# PIC32.net
KiCad netlist of a schematic drawn in EAGLE
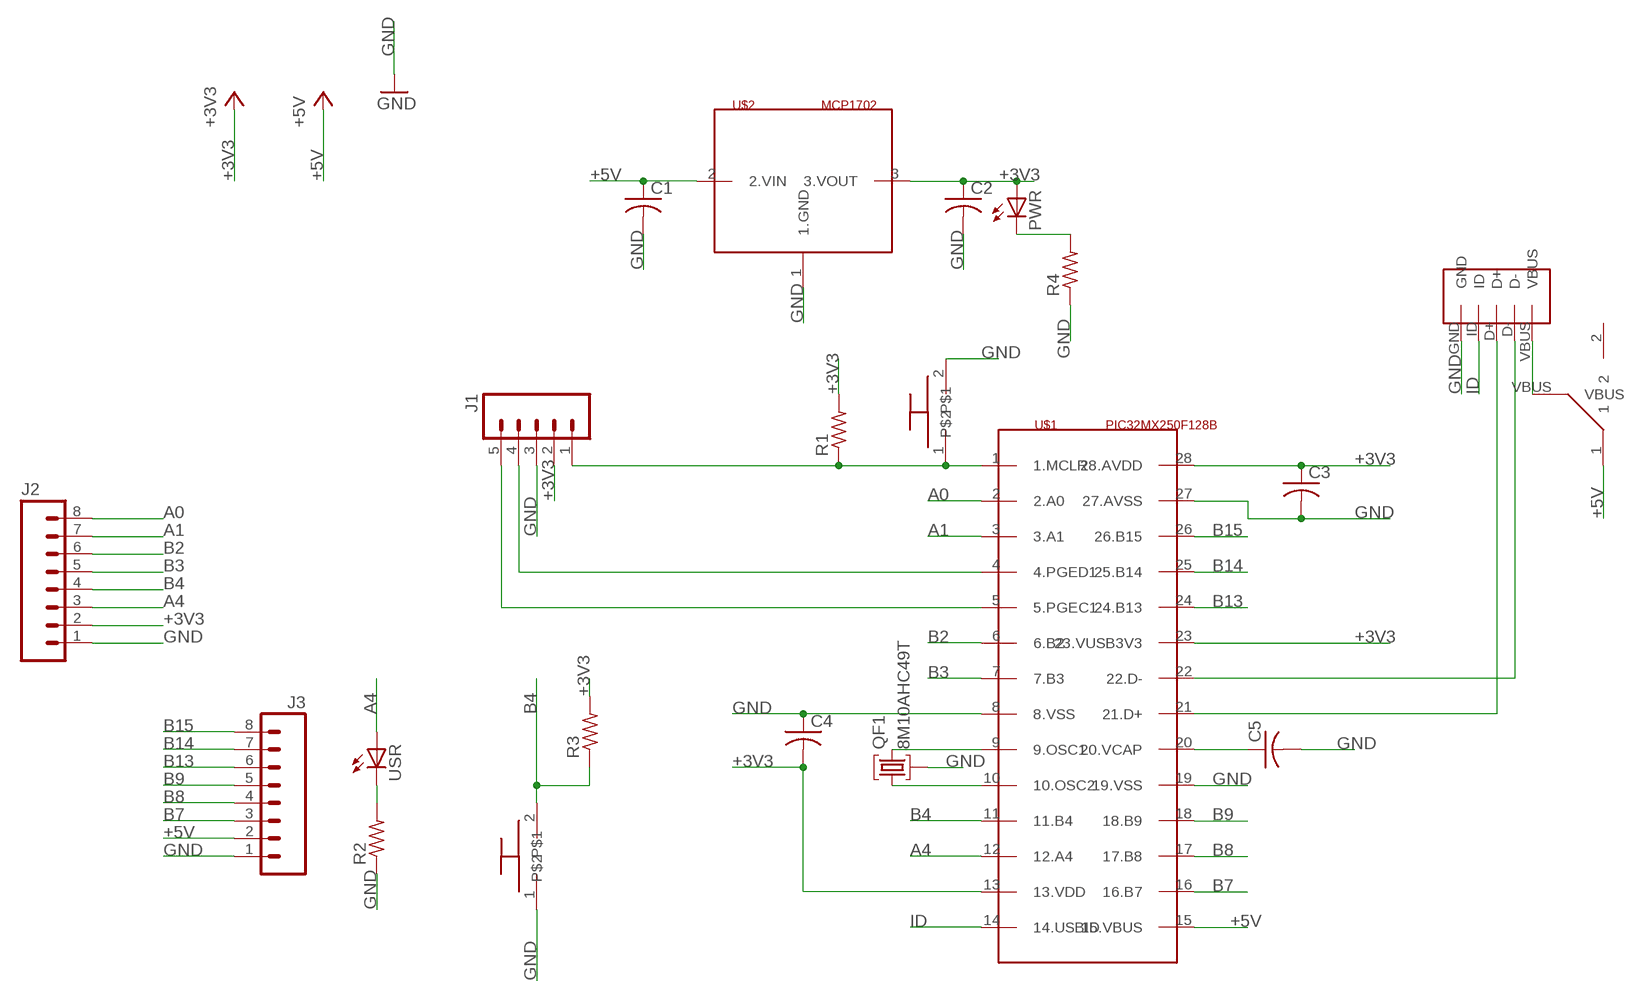
[diagram p0: schematic, sheet 1]

(export (version "E")
  (design (tool "Eeschema 10.0.6"))
  (components
    (comp (ref "C1")
      (value "C-US025-024X044")
      (footprint "eagle-import:C025-024X044")
      (libsource (lib "eagle-import") (part "C-US025-024X044"))
    )
    (comp (ref "C2")
      (value "C-US025-024X044")
      (footprint "eagle-import:C025-024X044")
      (libsource (lib "eagle-import") (part "C-US025-024X044"))
    )
    (comp (ref "C3")
      (value "C-US025-024X044")
      (footprint "eagle-import:C025-024X044")
      (libsource (lib "eagle-import") (part "C-US025-024X044"))
    )
    (comp (ref "C4")
      (value "C-US025-024X044")
      (footprint "eagle-import:C025-024X044")
      (libsource (lib "eagle-import") (part "C-US025-024X044"))
    )
    (comp (ref "C5")
      (value "C-US025-030X050")
      (footprint "eagle-import:C025-030X050")
      (libsource (lib "eagle-import") (part "C-US025-030X050"))
    )
    (comp (ref "J1")
      (value "M05PTH")
      (footprint "eagle-import:1X05")
      (libsource (lib "eagle-import") (part "M05PTH"))
    )
    (comp (ref "J2")
      (value "M08")
      (footprint "eagle-import:1X08_ROUND")
      (libsource (lib "eagle-import") (part "M08"))
    )
    (comp (ref "J3")
      (value "M08")
      (footprint "eagle-import:1X08_ROUND")
      (libsource (lib "eagle-import") (part "M08"))
    )
    (comp (ref "PWR")
      (value "LED3MM")
      (footprint "eagle-import:LED3MM")
      (libsource (lib "eagle-import") (part "LED3MM"))
    )
    (comp (ref "QF1")
      (value "8M10AHC49T")
      (footprint "eagle-import:HC49U")
      (libsource (lib "eagle-import") (part "8M10AHC49T"))
    )
    (comp (ref "R1")
      (value "R-US_0207/10")
      (footprint "eagle-import:0207_10")
      (libsource (lib "eagle-import") (part "R-US_0207/10"))
    )
    (comp (ref "R2")
      (value "R-US_0207/10")
      (footprint "eagle-import:0207_10")
      (libsource (lib "eagle-import") (part "R-US_0207/10"))
    )
    (comp (ref "R3")
      (value "R-US_0207/10")
      (footprint "eagle-import:0207_10")
      (libsource (lib "eagle-import") (part "R-US_0207/10"))
    )
    (comp (ref "R4")
      (value "R-US_0207/10")
      (footprint "eagle-import:0207_10")
      (libsource (lib "eagle-import") (part "R-US_0207/10"))
    )
    (comp (ref "RESET")
      (value "PUSHBUTTON")
      (footprint "eagle-import:PUSHBUTTON")
      (libsource (lib "eagle-import") (part "PUSHBUTTON"))
    )
    (comp (ref "U$1")
      (value "PIC32MX250F128B")
      (footprint "eagle-import:DIL28-3")
      (libsource (lib "eagle-import") (part "PIC32MX250F128B"))
    )
    (comp (ref "U$2")
      (value "MCP1702")
      (footprint "eagle-import:TO92-EBC")
      (libsource (lib "eagle-import") (part "MCP1702"))
    )
    (comp (ref "U$4")
      (value "USB")
      (footprint "eagle-import:USB-MB-H")
      (libsource (lib "eagle-import") (part "USB"))
    )
    (comp (ref "U$6")
      (value "SLIDESWITCH")
      (footprint "eagle-import:SLIDESWITCH")
      (libsource (lib "eagle-import") (part "SLIDESWITCH"))
    )
    (comp (ref "USER")
      (value "PUSHBUTTON")
      (footprint "eagle-import:PUSHBUTTON")
      (libsource (lib "eagle-import") (part "PUSHBUTTON"))
    )
    (comp (ref "USR")
      (value "LED3MM")
      (footprint "eagle-import:LED3MM")
      (libsource (lib "eagle-import") (part "LED3MM"))
    )
  )
  (nets
    (net (code "1") (name "+3V3") (class "Default")
      (node (ref "C2") (pin "1") (pinfunction "1_1") (pintype "passive"))
      (node (ref "C3") (pin "1") (pinfunction "1_1") (pintype "passive"))
      (node (ref "C4") (pin "2") (pinfunction "2_2") (pintype "passive"))
      (node (ref "J1") (pin "2") (pinfunction "2_2") (pintype "passive"))
      (node (ref "J2") (pin "2") (pinfunction "2_2") (pintype "passive"))
      (node (ref "PWR") (pin "A") (pinfunction "A_A") (pintype "passive"))
      (node (ref "R1") (pin "2") (pinfunction "2_2") (pintype "passive"))
      (node (ref "R3") (pin "2") (pinfunction "2_2") (pintype "passive"))
      (node (ref "U$1") (pin "13") (pinfunction "13.VDD_13") (pintype "bidirectional"))
      (node (ref "U$1") (pin "23") (pinfunction "23.VUSB3V3_23") (pintype "bidirectional"))
      (node (ref "U$1") (pin "28") (pinfunction "28.AVDD_28") (pintype "bidirectional"))
      (node (ref "U$2") (pin "3") (pinfunction "3.VOUT_3") (pintype "bidirectional"))
    )
    (net (code "2") (name "+5V") (class "Default")
      (node (ref "C1") (pin "1") (pinfunction "1_1") (pintype "passive"))
      (node (ref "J3") (pin "2") (pinfunction "2_2") (pintype "passive"))
      (node (ref "U$1") (pin "15") (pinfunction "15.VBUS_15") (pintype "bidirectional"))
      (node (ref "U$2") (pin "2") (pinfunction "2.VIN_2") (pintype "bidirectional"))
      (node (ref "U$6") (pin "1") (pinfunction "1_1") (pintype "bidirectional"))
    )
    (net (code "3") (name "/A0") (class "Default")
      (node (ref "J2") (pin "8") (pinfunction "8_8") (pintype "passive"))
      (node (ref "U$1") (pin "2") (pinfunction "2.A0_2") (pintype "bidirectional"))
    )
    (net (code "4") (name "/A1") (class "Default")
      (node (ref "J2") (pin "7") (pinfunction "7_7") (pintype "passive"))
      (node (ref "U$1") (pin "3") (pinfunction "3.A1_3") (pintype "bidirectional"))
    )
    (net (code "5") (name "/A4") (class "Default")
      (node (ref "J2") (pin "3") (pinfunction "3_3") (pintype "passive"))
      (node (ref "U$1") (pin "12") (pinfunction "12.A4_12") (pintype "bidirectional"))
      (node (ref "USR") (pin "A") (pinfunction "A_A") (pintype "passive"))
    )
    (net (code "6") (name "/B2") (class "Default")
      (node (ref "J2") (pin "6") (pinfunction "6_6") (pintype "passive"))
      (node (ref "U$1") (pin "6") (pinfunction "6.B2_6") (pintype "bidirectional"))
    )
    (net (code "7") (name "/B3") (class "Default")
      (node (ref "J2") (pin "5") (pinfunction "5_5") (pintype "passive"))
      (node (ref "U$1") (pin "7") (pinfunction "7.B3_7") (pintype "bidirectional"))
    )
    (net (code "8") (name "/B4") (class "Default")
      (node (ref "J2") (pin "4") (pinfunction "4_4") (pintype "passive"))
      (node (ref "R3") (pin "1") (pinfunction "1_1") (pintype "passive"))
      (node (ref "U$1") (pin "11") (pinfunction "11.B4_11") (pintype "bidirectional"))
      (node (ref "USER") (pin "2") (pinfunction "P$2_2") (pintype "bidirectional"))
    )
    (net (code "9") (name "/B7") (class "Default")
      (node (ref "J3") (pin "3") (pinfunction "3_3") (pintype "passive"))
      (node (ref "U$1") (pin "16") (pinfunction "16.B7_16") (pintype "bidirectional"))
    )
    (net (code "10") (name "/B8") (class "Default")
      (node (ref "J3") (pin "4") (pinfunction "4_4") (pintype "passive"))
      (node (ref "U$1") (pin "17") (pinfunction "17.B8_17") (pintype "bidirectional"))
    )
    (net (code "11") (name "/B9") (class "Default")
      (node (ref "J3") (pin "5") (pinfunction "5_5") (pintype "passive"))
      (node (ref "U$1") (pin "18") (pinfunction "18.B9_18") (pintype "bidirectional"))
    )
    (net (code "12") (name "/B13") (class "Default")
      (node (ref "J3") (pin "6") (pinfunction "6_6") (pintype "passive"))
      (node (ref "U$1") (pin "24") (pinfunction "24.B13_24") (pintype "bidirectional"))
    )
    (net (code "13") (name "/B14") (class "Default")
      (node (ref "J3") (pin "7") (pinfunction "7_7") (pintype "passive"))
      (node (ref "U$1") (pin "25") (pinfunction "25.B14_25") (pintype "bidirectional"))
    )
    (net (code "14") (name "/B15") (class "Default")
      (node (ref "J3") (pin "8") (pinfunction "8_8") (pintype "passive"))
      (node (ref "U$1") (pin "26") (pinfunction "26.B15_26") (pintype "bidirectional"))
    )
    (net (code "15") (name "/ID") (class "Default")
      (node (ref "U$1") (pin "14") (pinfunction "14.USBID_14") (pintype "bidirectional"))
      (node (ref "U$4") (pin "ID") (pinfunction "ID_ID") (pintype "bidirectional"))
    )
    (net (code "16") (name "GND") (class "Default")
      (node (ref "C1") (pin "2") (pinfunction "2_2") (pintype "passive"))
      (node (ref "C2") (pin "2") (pinfunction "2_2") (pintype "passive"))
      (node (ref "C3") (pin "2") (pinfunction "2_2") (pintype "passive"))
      (node (ref "C4") (pin "1") (pinfunction "1_1") (pintype "passive"))
      (node (ref "C5") (pin "2") (pinfunction "2_2") (pintype "passive"))
      (node (ref "J1") (pin "3") (pinfunction "3_3") (pintype "passive"))
      (node (ref "J2") (pin "1") (pinfunction "1_1") (pintype "passive"))
      (node (ref "J3") (pin "1") (pinfunction "1_1") (pintype "passive"))
      (node (ref "QF1") (pin "2") (pinfunction "2_2") (pintype "passive"))
      (node (ref "R2") (pin "1") (pinfunction "1_1") (pintype "passive"))
      (node (ref "R4") (pin "1") (pinfunction "1_1") (pintype "passive"))
      (node (ref "RESET") (pin "2") (pinfunction "P$2_2") (pintype "bidirectional"))
      (node (ref "U$1") (pin "19") (pinfunction "19.VSS_19") (pintype "bidirectional"))
      (node (ref "U$1") (pin "27") (pinfunction "27.AVSS_27") (pintype "bidirectional"))
      (node (ref "U$1") (pin "8") (pinfunction "8.VSS_8") (pintype "bidirectional"))
      (node (ref "U$2") (pin "1") (pinfunction "1.GND_1") (pintype "bidirectional"))
      (node (ref "U$4") (pin "GND") (pinfunction "GND_GND") (pintype "bidirectional"))
      (node (ref "USER") (pin "1") (pinfunction "P$1_1") (pintype "bidirectional"))
    )
    (net (code "17") (name "Net-(PWR-C)") (class "Default")
      (node (ref "PWR") (pin "K") (pinfunction "C_K") (pintype "passive"))
      (node (ref "R4") (pin "2") (pinfunction "2_2") (pintype "passive"))
    )
    (net (code "18") (name "Net-(RESET-P$1)") (class "Default")
      (node (ref "J1") (pin "1") (pinfunction "1_1") (pintype "passive"))
      (node (ref "R1") (pin "1") (pinfunction "1_1") (pintype "passive"))
      (node (ref "RESET") (pin "1") (pinfunction "P$1_1") (pintype "bidirectional"))
      (node (ref "U$1") (pin "1") (pinfunction "1.MCLR_1") (pintype "bidirectional"))
    )
    (net (code "19") (name "Net-(U$1-4.PGED1)") (class "Default")
      (node (ref "J1") (pin "4") (pinfunction "4_4") (pintype "passive"))
      (node (ref "U$1") (pin "4") (pinfunction "4.PGED1_4") (pintype "bidirectional"))
    )
    (net (code "20") (name "Net-(U$1-5.PGEC1)") (class "Default")
      (node (ref "J1") (pin "5") (pinfunction "5_5") (pintype "passive"))
      (node (ref "U$1") (pin "5") (pinfunction "5.PGEC1_5") (pintype "bidirectional"))
    )
    (net (code "21") (name "Net-(U$1-9.OSC1)") (class "Default")
      (node (ref "QF1") (pin "3") (pinfunction "3_3") (pintype "passive"))
      (node (ref "U$1") (pin "9") (pinfunction "9.OSC1_9") (pintype "bidirectional"))
    )
    (net (code "22") (name "Net-(U$1-10.OSC2)") (class "Default")
      (node (ref "QF1") (pin "1") (pinfunction "1_1") (pintype "passive"))
      (node (ref "U$1") (pin "10") (pinfunction "10.OSC2_10") (pintype "bidirectional"))
    )
    (net (code "23") (name "Net-(U$1-20.VCAP)") (class "Default")
      (node (ref "C5") (pin "1") (pinfunction "1_1") (pintype "passive"))
      (node (ref "U$1") (pin "20") (pinfunction "20.VCAP_20") (pintype "bidirectional"))
    )
    (net (code "24") (name "Net-(U$1-21.D+)") (class "Default")
      (node (ref "U$1") (pin "21") (pinfunction "21.D+_21") (pintype "bidirectional"))
      (node (ref "U$4") (pin "D+") (pinfunction "D+_D+") (pintype "bidirectional"))
    )
    (net (code "25") (name "Net-(U$1-22.D-)") (class "Default")
      (node (ref "U$1") (pin "22") (pinfunction "22.D-_22") (pintype "bidirectional"))
      (node (ref "U$4") (pin "D-") (pinfunction "D-_D-") (pintype "bidirectional"))
    )
    (net (code "26") (name "Net-(U$4-PadVBUS)") (class "Default")
      (node (ref "U$4") (pin "VBUS") (pinfunction "VBUS_VBUS") (pintype "bidirectional"))
      (node (ref "U$6") (pin "VBUS") (pinfunction "VBUS_VBUS") (pintype "bidirectional"))
    )
    (net (code "27") (name "Net-(USR-C)") (class "Default")
      (node (ref "R2") (pin "2") (pinfunction "2_2") (pintype "passive"))
      (node (ref "USR") (pin "K") (pinfunction "C_K") (pintype "passive"))
    )
    (net (code "28") (name "unconnected-(U$6-Pad2)") (class "Default")
      (node (ref "U$6") (pin "2") (pinfunction "2_2") (pintype "bidirectional"))
    )
  )
)
